# PowerToSer.net
KiCad netlist of a schematic drawn in Altium Designer
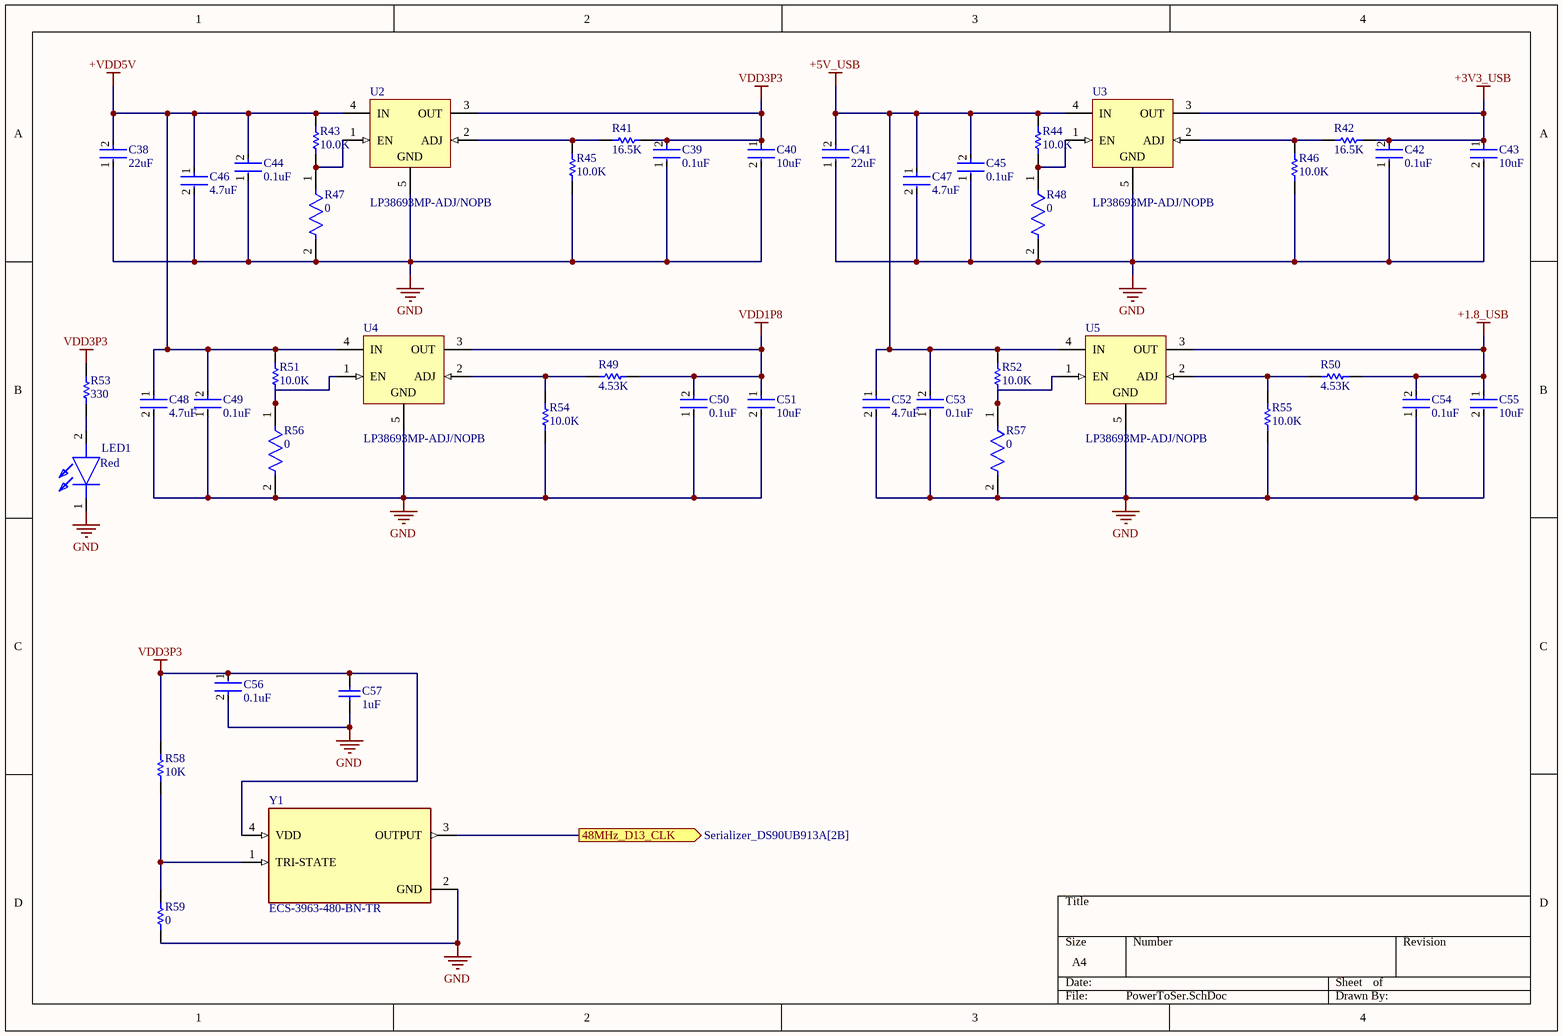
[diagram p0: PowerToSer.SchDoc]

(export (version "E")
  (design (tool "Eeschema 10.0.6"))
  (components
    (comp (ref "C38")
      (value "22uF")
      (footprint "FP-GCM32E-0_3-IPC_B")
      (description "Ceramic Capacitor for Automotive 22uF ±10% 16VDC X7R 1210 Embossed T/R")
      (fields (field (name "VOLTAGE") "16V") (field (name "TOLERANCE") "10%"))
      (libsource (lib "Altium Content Vault") (part "f23184f103b6ebe33a8c269c53dcba6"))
    )
    (comp (ref "C39")
      (value "0.1uF")
      (footprint "FP-GRM15-MFG")
      (description "CAP CER 0.1UF 16V X7R 0402")
      (fields (field (name "MANUFACTURER PART NUMBER") "GRM155R71C104KA88D") (field (name "TOLERANCE") "10%"))
      (libsource (lib "Altium Content Vault") (part "236180d848d6139a670b325ea6854c9"))
    )
    (comp (ref "C40")
      (value "10uF")
      (footprint "FP-GRM21B-0_1-IPC_C")
      (description "Chip Multilayer Ceramic Capacitors for General Purpose, 0805, 10uF, X5R, 15%, 10%, 16V")
      (fields (field (name "TOLERANCE") "10%") (field (name "VOLTAGE") "16V"))
      (libsource (lib "Altium Content Vault") (part "b4654b650e69147ec39a6b967a45e02"))
    )
    (comp (ref "C41")
      (value "22uF")
      (footprint "FP-GCM32E-0_3-IPC_B")
      (description "Ceramic Capacitor for Automotive 22uF ±10% 16VDC X7R 1210 Embossed T/R")
      (fields (field (name "VOLTAGE") "16V") (field (name "TOLERANCE") "10%"))
      (libsource (lib "Altium Content Vault") (part "f23184f103b6ebe33a8c269c53dcba6"))
    )
    (comp (ref "C42")
      (value "0.1uF")
      (footprint "FP-GRM15-MFG")
      (description "CAP CER 0.1UF 16V X7R 0402")
      (fields (field (name "MANUFACTURER PART NUMBER") "GRM155R71C104KA88D") (field (name "TOLERANCE") "10%"))
      (libsource (lib "Altium Content Vault") (part "236180d848d6139a670b325ea6854c9"))
    )
    (comp (ref "C43")
      (value "10uF")
      (footprint "FP-GRM21B-0_1-IPC_C")
      (description "Chip Multilayer Ceramic Capacitors for General Purpose, 0805, 10uF, X5R, 15%, 10%, 16V")
      (fields (field (name "TOLERANCE") "10%") (field (name "VOLTAGE") "16V"))
      (libsource (lib "Altium Content Vault") (part "b4654b650e69147ec39a6b967a45e02"))
    )
    (comp (ref "C44")
      (value "0.1uF")
      (footprint "FP-GRM15-MFG")
      (description "CAP CER 0.1UF 16V X7R 0402")
      (fields (field (name "MANUFACTURER PART NUMBER") "GRM155R71C104KA88D") (field (name "TOLERANCE") "10%"))
      (libsource (lib "Altium Content Vault") (part "236180d848d6139a670b325ea6854c9"))
    )
    (comp (ref "C45")
      (value "0.1uF")
      (footprint "FP-GRM15-MFG")
      (description "CAP CER 0.1UF 16V X7R 0402")
      (fields (field (name "MANUFACTURER PART NUMBER") "GRM155R71C104KA88D") (field (name "TOLERANCE") "10%"))
      (libsource (lib "Altium Content Vault") (part "236180d848d6139a670b325ea6854c9"))
    )
    (comp (ref "C46")
      (value "4.7uF")
      (footprint "FP-GRM21B-0_15-MFG")
      (description "CAP CER 4.7UF 16V X7R 0805")
      (fields (field (name "VOLTAGE") "16V") (field (name "TOLERANCE") "10%"))
      (libsource (lib "Altium Content Vault") (part "b4654b650e69147ec39a6b967a45e02"))
    )
    (comp (ref "C47")
      (value "4.7uF")
      (footprint "FP-GRM21B-0_15-MFG")
      (description "CAP CER 4.7UF 16V X7R 0805")
      (fields (field (name "VOLTAGE") "16V") (field (name "TOLERANCE") "10%"))
      (libsource (lib "Altium Content Vault") (part "b4654b650e69147ec39a6b967a45e02"))
    )
    (comp (ref "C48")
      (value "4.7uF")
      (footprint "FP-GRM21B-0_15-MFG")
      (description "CAP CER 4.7UF 16V X7R 0805")
      (fields (field (name "VOLTAGE") "16V") (field (name "TOLERANCE") "10%"))
      (libsource (lib "Altium Content Vault") (part "b4654b650e69147ec39a6b967a45e02"))
    )
    (comp (ref "C49")
      (value "0.1uF")
      (footprint "FP-GRM15-MFG")
      (description "CAP CER 0.1UF 16V X7R 0402")
      (fields (field (name "MANUFACTURER PART NUMBER") "GRM155R71C104KA88D") (field (name "TOLERANCE") "10%"))
      (libsource (lib "Altium Content Vault") (part "236180d848d6139a670b325ea6854c9"))
    )
    (comp (ref "C50")
      (value "0.1uF")
      (footprint "FP-GRM15-MFG")
      (description "CAP CER 0.1UF 16V X7R 0402")
      (fields (field (name "MANUFACTURER PART NUMBER") "GRM155R71C104KA88D") (field (name "TOLERANCE") "10%"))
      (libsource (lib "Altium Content Vault") (part "236180d848d6139a670b325ea6854c9"))
    )
    (comp (ref "C51")
      (value "10uF")
      (footprint "FP-GRM21B-0_1-IPC_C")
      (description "Chip Multilayer Ceramic Capacitors for General Purpose, 0805, 10uF, X5R, 15%, 10%, 16V")
      (fields (field (name "TOLERANCE") "10%") (field (name "VOLTAGE") "16V"))
      (libsource (lib "Altium Content Vault") (part "b4654b650e69147ec39a6b967a45e02"))
    )
    (comp (ref "C52")
      (value "4.7uF")
      (footprint "FP-GRM21B-0_15-MFG")
      (description "CAP CER 4.7UF 16V X7R 0805")
      (fields (field (name "VOLTAGE") "16V") (field (name "TOLERANCE") "10%"))
      (libsource (lib "Altium Content Vault") (part "b4654b650e69147ec39a6b967a45e02"))
    )
    (comp (ref "C53")
      (value "0.1uF")
      (footprint "FP-GRM15-MFG")
      (description "CAP CER 0.1UF 16V X7R 0402")
      (fields (field (name "MANUFACTURER PART NUMBER") "GRM155R71C104KA88D") (field (name "TOLERANCE") "10%"))
      (libsource (lib "Altium Content Vault") (part "236180d848d6139a670b325ea6854c9"))
    )
    (comp (ref "C54")
      (value "0.1uF")
      (footprint "FP-GRM15-MFG")
      (description "CAP CER 0.1UF 16V X7R 0402")
      (fields (field (name "MANUFACTURER PART NUMBER") "GRM155R71C104KA88D") (field (name "TOLERANCE") "10%"))
      (libsource (lib "Altium Content Vault") (part "236180d848d6139a670b325ea6854c9"))
    )
    (comp (ref "C55")
      (value "10uF")
      (footprint "FP-GRM21B-0_1-IPC_C")
      (description "Chip Multilayer Ceramic Capacitors for General Purpose, 0805, 10uF, X5R, 15%, 10%, 16V")
      (fields (field (name "TOLERANCE") "10%") (field (name "VOLTAGE") "16V"))
      (libsource (lib "Altium Content Vault") (part "b4654b650e69147ec39a6b967a45e02"))
    )
    (comp (ref "C56")
      (value "0.1uF")
      (footprint "FP-GRM15-MFG")
      (description "CAP CER 0.1UF 16V X7R 0402")
      (fields (field (name "MANUFACTURER PART NUMBER") "GRM155R71C104KA88D") (field (name "TOLERANCE") "10%"))
      (libsource (lib "Altium Content Vault") (part "236180d848d6139a670b325ea6854c9"))
    )
    (comp (ref "C57")
      (value "1uF")
      (footprint "CAPC1608X90X35ML10T15")
      (fields (field (name "MANUFACTURER") "Murata") (field (name "PART NUMBER") "GRM188R71E105KA12D"))
      (libsource (lib "Altium Content Vault") (part "CAP"))
    )
    (comp (ref "LED1")
      (value "Red")
      (footprint "SerDes_Eval_Board_Footprints:LEDC1608X55N")
      (description "LED")
      (fields
        (field (name "MANUFACTURER_PART_NUMBER") "LTST-C191KRKT")
        (field (name "MOUSER PART NUMBER") "859-LTST-C191KRKT")
      )
      (libsource (lib "SerDes_Eval") (part "LTST-C191KRKT"))
    )
    (comp (ref "R41")
      (value "16.5K")
      (footprint "RESC1608X55X30LL15T15")
      (fields (field (name "MANUFACTURER") "Panasonic") (field (name "PART NUMBER") "ERJ-3EKF1652V"))
      (libsource (lib "Altium Content Vault") (part "RES"))
    )
    (comp (ref "R42")
      (value "16.5K")
      (footprint "RESC1608X55X30LL15T15")
      (fields (field (name "MANUFACTURER") "Panasonic") (field (name "PART NUMBER") "ERJ-3EKF1652V"))
      (libsource (lib "Altium Content Vault") (part "RES"))
    )
    (comp (ref "R43")
      (value "10.0K")
      (footprint "RESC1609X55X30LL15T15")
      (description "Chip Resistor, 10 KOhm, +/- 1%, 0.1 W, -55 to 155 degC, 0603 (1608 Metric), RoHS, Tape and Reel")
      (fields (field (name "TOLERANCE") "1%") (field (name "MANUFACTURER") "Panasonic"))
      (libsource (lib "Altium Content Vault") (part "RES-2"))
    )
    (comp (ref "R44")
      (value "10.0K")
      (footprint "RESC1609X55X30LL15T15")
      (description "Chip Resistor, 10 KOhm, +/- 1%, 0.1 W, -55 to 155 degC, 0603 (1608 Metric), RoHS, Tape and Reel")
      (fields (field (name "TOLERANCE") "1%") (field (name "MANUFACTURER") "Panasonic"))
      (libsource (lib "Altium Content Vault") (part "RES-2"))
    )
    (comp (ref "R45")
      (value "10.0K")
      (footprint "RESC1609X55X30LL15T15")
      (description "Chip Resistor, 10 KOhm, +/- 1%, 0.1 W, -55 to 155 degC, 0603 (1608 Metric), RoHS, Tape and Reel")
      (fields (field (name "TOLERANCE") "1%") (field (name "MANUFACTURER") "Panasonic"))
      (libsource (lib "Altium Content Vault") (part "RES-2"))
    )
    (comp (ref "R46")
      (value "10.0K")
      (footprint "RESC1609X55X30LL15T15")
      (description "Chip Resistor, 10 KOhm, +/- 1%, 0.1 W, -55 to 155 degC, 0603 (1608 Metric), RoHS, Tape and Reel")
      (fields (field (name "TOLERANCE") "1%") (field (name "MANUFACTURER") "Panasonic"))
      (libsource (lib "Altium Content Vault") (part "RES-2"))
    )
    (comp (ref "R47")
      (value "0")
      (footprint "FP-ERJ-3GEY0R00V-MFG")
      (description "RES SMD 0 OHM JUMPER 1/10W 0603")
      (fields (field (name "TOLERANCE") "5%") (field (name "MANUFACTURER PART NUMBER") "ERJ-3GEY0R00V"))
      (libsource (lib "Altium Content Vault") (part "1029c3af85768c4190bb7ad29bc67b5"))
    )
    (comp (ref "R48")
      (value "0")
      (footprint "FP-ERJ-3GEY0R00V-MFG")
      (description "RES SMD 0 OHM JUMPER 1/10W 0603")
      (fields (field (name "TOLERANCE") "5%") (field (name "MANUFACTURER PART NUMBER") "ERJ-3GEY0R00V"))
      (libsource (lib "Altium Content Vault") (part "1029c3af85768c4190bb7ad29bc67b5"))
    )
    (comp (ref "R49")
      (value "4.53K")
      (footprint "RESC1608X55X30ML15T15")
      (fields (field (name "PART NUMBER") "ERJ-3EKF4531V") (field (name "MANUFACTURER") "Panasonic"))
      (libsource (lib "Altium Content Vault") (part "RES"))
    )
    (comp (ref "R50")
      (value "4.53K")
      (footprint "RESC1608X55X30ML15T15")
      (fields (field (name "PART NUMBER") "ERJ-3EKF4531V") (field (name "MANUFACTURER") "Panasonic"))
      (libsource (lib "Altium Content Vault") (part "RES"))
    )
    (comp (ref "R51")
      (value "10.0K")
      (footprint "RESC1609X55X30LL15T15")
      (description "Chip Resistor, 10 KOhm, +/- 1%, 0.1 W, -55 to 155 degC, 0603 (1608 Metric), RoHS, Tape and Reel")
      (fields (field (name "TOLERANCE") "1%") (field (name "MANUFACTURER") "Panasonic"))
      (libsource (lib "Altium Content Vault") (part "RES-2"))
    )
    (comp (ref "R52")
      (value "10.0K")
      (footprint "RESC1609X55X30LL15T15")
      (description "Chip Resistor, 10 KOhm, +/- 1%, 0.1 W, -55 to 155 degC, 0603 (1608 Metric), RoHS, Tape and Reel")
      (fields (field (name "TOLERANCE") "1%") (field (name "MANUFACTURER") "Panasonic"))
      (libsource (lib "Altium Content Vault") (part "RES-2"))
    )
    (comp (ref "R53")
      (value "330")
      (footprint "RESC1005X40X25ML05T05")
      (fields (field (name "MANUFACTURER") "Panasonic") (field (name "PART NUMBER") "ERJ2RKF3300X"))
      (libsource (lib "Altium Content Vault") (part "RES"))
    )
    (comp (ref "R54")
      (value "10.0K")
      (footprint "RESC1609X55X30LL15T15")
      (description "Chip Resistor, 10 KOhm, +/- 1%, 0.1 W, -55 to 155 degC, 0603 (1608 Metric), RoHS, Tape and Reel")
      (fields (field (name "TOLERANCE") "1%") (field (name "MANUFACTURER") "Panasonic"))
      (libsource (lib "Altium Content Vault") (part "RES-2"))
    )
    (comp (ref "R55")
      (value "10.0K")
      (footprint "RESC1609X55X30LL15T15")
      (description "Chip Resistor, 10 KOhm, +/- 1%, 0.1 W, -55 to 155 degC, 0603 (1608 Metric), RoHS, Tape and Reel")
      (fields (field (name "TOLERANCE") "1%") (field (name "MANUFACTURER") "Panasonic"))
      (libsource (lib "Altium Content Vault") (part "RES-2"))
    )
    (comp (ref "R56")
      (value "0")
      (footprint "FP-ERJ-3GEY0R00V-MFG")
      (description "RES SMD 0 OHM JUMPER 1/10W 0603")
      (fields (field (name "TOLERANCE") "5%") (field (name "MANUFACTURER PART NUMBER") "ERJ-3GEY0R00V"))
      (libsource (lib "Altium Content Vault") (part "1029c3af85768c4190bb7ad29bc67b5"))
    )
    (comp (ref "R57")
      (value "0")
      (footprint "FP-ERJ-3GEY0R00V-MFG")
      (description "RES SMD 0 OHM JUMPER 1/10W 0603")
      (fields (field (name "TOLERANCE") "5%") (field (name "MANUFACTURER PART NUMBER") "ERJ-3GEY0R00V"))
      (libsource (lib "Altium Content Vault") (part "1029c3af85768c4190bb7ad29bc67b5"))
    )
    (comp (ref "R58")
      (value "10K")
      (footprint "RESC1005X40X25ML05T05")
      (fields (field (name "PART NUMBER") "ERJ-2GEJ103X") (field (name "MANUFACTURER") "Panasonic"))
      (libsource (lib "Altium Content Vault") (part "RES"))
    )
    (comp (ref "R59")
      (value "0")
      (footprint "RESC1005X40X25LL05T05")
      (description "Chip Resistor, 0 Ohm, 0.1 W, -55 to 155 degC, 0402 (1005 Metric), RoHS, Tape and Reel")
      (fields (field (name "MANUFACTURER") "Panasonic") (field (name "TOLERANCE") "5%"))
      (libsource (lib "Altium Content Vault") (part "RES-2"))
    )
    (comp (ref "U2")
      (value "LP38693MP-ADJ/NOPB")
      (footprint "NDC0005A_N")
      (fields (field (name "MANUFACTURER") "Texas Instruments"))
      (libsource (lib "Altium Content Vault") (part "PM-REG-LP38693ADJ-SOT5"))
    )
    (comp (ref "U3")
      (value "LP38693MP-ADJ/NOPB")
      (footprint "NDC0005A_N")
      (fields (field (name "MANUFACTURER") "Texas Instruments"))
      (libsource (lib "Altium Content Vault") (part "PM-REG-LP38693ADJ-SOT5"))
    )
    (comp (ref "U4")
      (value "LP38693MP-ADJ/NOPB")
      (footprint "NDC0005A_N")
      (fields (field (name "MANUFACTURER") "Texas Instruments"))
      (libsource (lib "Altium Content Vault") (part "PM-REG-LP38693ADJ-SOT5"))
    )
    (comp (ref "U5")
      (value "LP38693MP-ADJ/NOPB")
      (footprint "NDC0005A_N")
      (fields (field (name "MANUFACTURER") "Texas Instruments"))
      (libsource (lib "Altium Content Vault") (part "PM-REG-LP38693ADJ-SOT5"))
    )
    (comp (ref "Y1")
      (value "ECS-3963-480-BN-TR")
      (footprint "SerDes_Eval_Board_Footprints:OSC_ECS-3963-480-BN-TR")
      (description "miniature SMD crystal controlled oscillators")
      (libsource (lib "SerDes_Eval") (part "ECS-3963-480-BN-TR"))
    )
  )
  (nets
    (net (code "1") (name "+1.8_USB") (class "Default")
      (node (ref "C54") (pin "2") (pinfunction "2_2") (pintype "passive"))
      (node (ref "C55") (pin "1") (pinfunction "1_1") (pintype "passive"))
      (node (ref "R50") (pin "2") (pinfunction "2_2") (pintype "passive"))
      (node (ref "U5") (pin "3") (pinfunction "OUT_3") (pintype "power_in"))
    )
    (net (code "2") (name "+3V3_USB") (class "Default")
      (node (ref "C42") (pin "2") (pinfunction "2_2") (pintype "passive"))
      (node (ref "C43") (pin "1") (pinfunction "1_1") (pintype "passive"))
      (node (ref "R42") (pin "2") (pinfunction "2_2") (pintype "passive"))
      (node (ref "U3") (pin "3") (pinfunction "OUT_3") (pintype "power_in"))
    )
    (net (code "3") (name "+5V_USB") (class "Default")
      (node (ref "C41") (pin "2") (pinfunction "2_2") (pintype "passive"))
      (node (ref "C45") (pin "2") (pinfunction "2_2") (pintype "passive"))
      (node (ref "C47") (pin "1") (pinfunction "1_1") (pintype "passive"))
      (node (ref "C52") (pin "1") (pinfunction "1_1") (pintype "passive"))
      (node (ref "C53") (pin "2") (pinfunction "2_2") (pintype "passive"))
      (node (ref "R44") (pin "1") (pinfunction "1_1") (pintype "passive"))
      (node (ref "R52") (pin "1") (pinfunction "1_1") (pintype "passive"))
      (node (ref "U3") (pin "4") (pinfunction "IN_4") (pintype "power_in"))
      (node (ref "U5") (pin "4") (pinfunction "IN_4") (pintype "power_in"))
    )
    (net (code "4") (name "+VDD5V") (class "Default")
      (node (ref "C38") (pin "2") (pinfunction "2_2") (pintype "passive"))
      (node (ref "C44") (pin "2") (pinfunction "2_2") (pintype "passive"))
      (node (ref "C46") (pin "1") (pinfunction "1_1") (pintype "passive"))
      (node (ref "C48") (pin "1") (pinfunction "1_1") (pintype "passive"))
      (node (ref "C49") (pin "2") (pinfunction "2_2") (pintype "passive"))
      (node (ref "R43") (pin "1") (pinfunction "1_1") (pintype "passive"))
      (node (ref "R51") (pin "1") (pinfunction "1_1") (pintype "passive"))
      (node (ref "U2") (pin "4") (pinfunction "IN_4") (pintype "power_in"))
      (node (ref "U4") (pin "4") (pinfunction "IN_4") (pintype "power_in"))
    )
    (net (code "5") (name "/48MHz_D13_CLK") (class "Default")
      (node (ref "Y1") (pin "3") (pinfunction "OUTPUT_3") (pintype "output"))
    )
    (net (code "6") (name "GND") (class "Default")
      (node (ref "C38") (pin "1") (pinfunction "1_1") (pintype "passive"))
      (node (ref "C39") (pin "1") (pinfunction "1_1") (pintype "passive"))
      (node (ref "C40") (pin "2") (pinfunction "2_2") (pintype "passive"))
      (node (ref "C41") (pin "1") (pinfunction "1_1") (pintype "passive"))
      (node (ref "C42") (pin "1") (pinfunction "1_1") (pintype "passive"))
      (node (ref "C43") (pin "2") (pinfunction "2_2") (pintype "passive"))
      (node (ref "C44") (pin "1") (pinfunction "1_1") (pintype "passive"))
      (node (ref "C45") (pin "1") (pinfunction "1_1") (pintype "passive"))
      (node (ref "C46") (pin "2") (pinfunction "2_2") (pintype "passive"))
      (node (ref "C47") (pin "2") (pinfunction "2_2") (pintype "passive"))
      (node (ref "C48") (pin "2") (pinfunction "2_2") (pintype "passive"))
      (node (ref "C49") (pin "1") (pinfunction "1_1") (pintype "passive"))
      (node (ref "C50") (pin "1") (pinfunction "1_1") (pintype "passive"))
      (node (ref "C51") (pin "2") (pinfunction "2_2") (pintype "passive"))
      (node (ref "C52") (pin "2") (pinfunction "2_2") (pintype "passive"))
      (node (ref "C53") (pin "1") (pinfunction "1_1") (pintype "passive"))
      (node (ref "C54") (pin "1") (pinfunction "1_1") (pintype "passive"))
      (node (ref "C55") (pin "2") (pinfunction "2_2") (pintype "passive"))
      (node (ref "C56") (pin "2") (pinfunction "2_2") (pintype "passive"))
      (node (ref "C57") (pin "2") (pinfunction "2_2") (pintype "passive"))
      (node (ref "LED1") (pin "1") (pinfunction "K_1") (pintype "passive"))
      (node (ref "R45") (pin "2") (pinfunction "2_2") (pintype "passive"))
      (node (ref "R46") (pin "2") (pinfunction "2_2") (pintype "passive"))
      (node (ref "R47") (pin "2") (pinfunction "2_2") (pintype "passive"))
      (node (ref "R48") (pin "2") (pinfunction "2_2") (pintype "passive"))
      (node (ref "R54") (pin "2") (pinfunction "2_2") (pintype "passive"))
      (node (ref "R55") (pin "2") (pinfunction "2_2") (pintype "passive"))
      (node (ref "R56") (pin "2") (pinfunction "2_2") (pintype "passive"))
      (node (ref "R57") (pin "2") (pinfunction "2_2") (pintype "passive"))
      (node (ref "R59") (pin "2") (pinfunction "2_2") (pintype "passive"))
      (node (ref "U2") (pin "5") (pinfunction "GND_5") (pintype "power_in"))
      (node (ref "U3") (pin "5") (pinfunction "GND_5") (pintype "power_in"))
      (node (ref "U4") (pin "5") (pinfunction "GND_5") (pintype "power_in"))
      (node (ref "U5") (pin "5") (pinfunction "GND_5") (pintype "power_in"))
      (node (ref "Y1") (pin "2") (pinfunction "GND_2") (pintype "power_in"))
    )
    (net (code "7") (name "Net-(LED1-A)") (class "Default")
      (node (ref "LED1") (pin "2") (pinfunction "A_2") (pintype "passive"))
      (node (ref "R53") (pin "2") (pinfunction "2_2") (pintype "passive"))
    )
    (net (code "8") (name "Net-(U2-ADJ)") (class "Default")
      (node (ref "R41") (pin "1") (pinfunction "1_1") (pintype "passive"))
      (node (ref "R45") (pin "1") (pinfunction "1_1") (pintype "passive"))
      (node (ref "U2") (pin "2") (pinfunction "ADJ_2") (pintype "input"))
    )
    (net (code "9") (name "Net-(U2-EN)") (class "Default")
      (node (ref "R43") (pin "2") (pinfunction "2_2") (pintype "passive"))
      (node (ref "R47") (pin "1") (pinfunction "1_1") (pintype "passive"))
      (node (ref "U2") (pin "1") (pinfunction "EN_1") (pintype "input"))
    )
    (net (code "10") (name "Net-(U3-ADJ)") (class "Default")
      (node (ref "R42") (pin "1") (pinfunction "1_1") (pintype "passive"))
      (node (ref "R46") (pin "1") (pinfunction "1_1") (pintype "passive"))
      (node (ref "U3") (pin "2") (pinfunction "ADJ_2") (pintype "input"))
    )
    (net (code "11") (name "Net-(U3-EN)") (class "Default")
      (node (ref "R44") (pin "2") (pinfunction "2_2") (pintype "passive"))
      (node (ref "R48") (pin "1") (pinfunction "1_1") (pintype "passive"))
      (node (ref "U3") (pin "1") (pinfunction "EN_1") (pintype "input"))
    )
    (net (code "12") (name "Net-(U4-ADJ)") (class "Default")
      (node (ref "R49") (pin "1") (pinfunction "1_1") (pintype "passive"))
      (node (ref "R54") (pin "1") (pinfunction "1_1") (pintype "passive"))
      (node (ref "U4") (pin "2") (pinfunction "ADJ_2") (pintype "input"))
    )
    (net (code "13") (name "Net-(U4-EN)") (class "Default")
      (node (ref "R51") (pin "2") (pinfunction "2_2") (pintype "passive"))
      (node (ref "R56") (pin "1") (pinfunction "1_1") (pintype "passive"))
      (node (ref "U4") (pin "1") (pinfunction "EN_1") (pintype "input"))
    )
    (net (code "14") (name "Net-(U5-ADJ)") (class "Default")
      (node (ref "R50") (pin "1") (pinfunction "1_1") (pintype "passive"))
      (node (ref "R55") (pin "1") (pinfunction "1_1") (pintype "passive"))
      (node (ref "U5") (pin "2") (pinfunction "ADJ_2") (pintype "input"))
    )
    (net (code "15") (name "Net-(U5-EN)") (class "Default")
      (node (ref "R52") (pin "2") (pinfunction "2_2") (pintype "passive"))
      (node (ref "R57") (pin "1") (pinfunction "1_1") (pintype "passive"))
      (node (ref "U5") (pin "1") (pinfunction "EN_1") (pintype "input"))
    )
    (net (code "16") (name "Net-(Y1-TRI-STATE)") (class "Default")
      (node (ref "R58") (pin "2") (pinfunction "2_2") (pintype "passive"))
      (node (ref "R59") (pin "1") (pinfunction "1_1") (pintype "passive"))
      (node (ref "Y1") (pin "1") (pinfunction "TRI-STATE_1") (pintype "input"))
    )
    (net (code "17") (name "VDD1P8") (class "Default")
      (node (ref "C50") (pin "2") (pinfunction "2_2") (pintype "passive"))
      (node (ref "C51") (pin "1") (pinfunction "1_1") (pintype "passive"))
      (node (ref "R49") (pin "2") (pinfunction "2_2") (pintype "passive"))
      (node (ref "U4") (pin "3") (pinfunction "OUT_3") (pintype "power_in"))
    )
    (net (code "18") (name "VDD3P3") (class "Default")
      (node (ref "C39") (pin "2") (pinfunction "2_2") (pintype "passive"))
      (node (ref "C40") (pin "1") (pinfunction "1_1") (pintype "passive"))
      (node (ref "C56") (pin "1") (pinfunction "1_1") (pintype "passive"))
      (node (ref "C57") (pin "1") (pinfunction "1_1") (pintype "passive"))
      (node (ref "R41") (pin "2") (pinfunction "2_2") (pintype "passive"))
      (node (ref "R53") (pin "1") (pinfunction "1_1") (pintype "passive"))
      (node (ref "R58") (pin "1") (pinfunction "1_1") (pintype "passive"))
      (node (ref "U2") (pin "3") (pinfunction "OUT_3") (pintype "power_in"))
      (node (ref "Y1") (pin "4") (pinfunction "VDD_4") (pintype "input"))
    )
  )
)
